# eBus_RS232_schematic.net
KiCad netlist of a schematic drawn in EAGLE
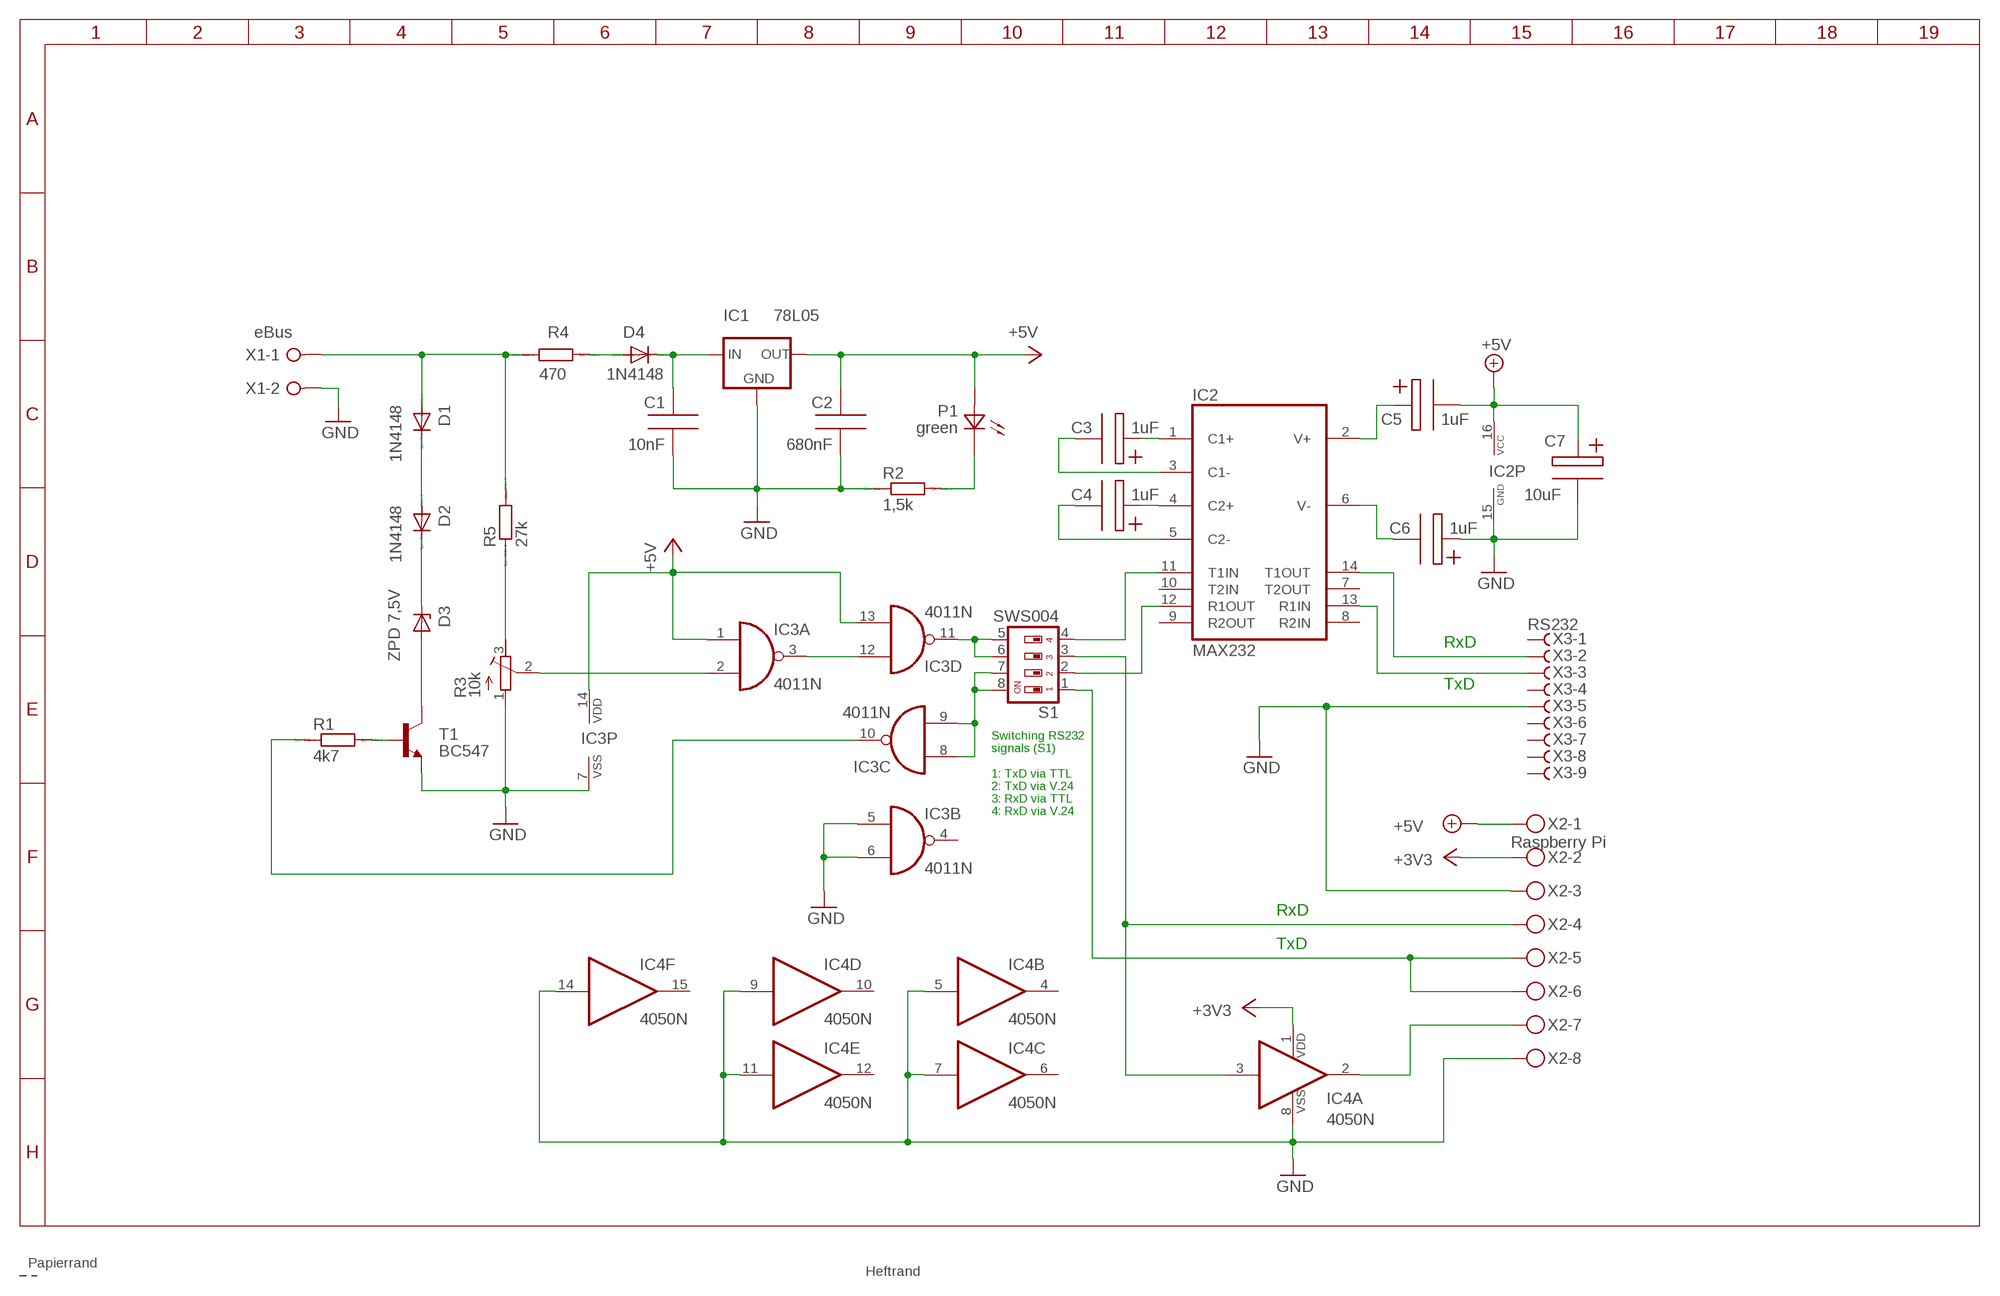
[diagram p0: schematic, sheet 1]

(export (version "E")
  (design (tool "Eeschema 10.0.6"))
  (components
    (comp (ref "C1")
      (value "10nF")
      (footprint "eagle-import:KONDENSATOR_KAPAZITAET_ALLGEMEIN")
      (libsource (lib "eagle-import") (part "KONDENSATOR_KAPAZITAET_ALLGEMEIN"))
    )
    (comp (ref "C2")
      (value "680nF")
      (footprint "eagle-import:KONDENSATOR_KAPAZITAET_ALLGEMEIN")
      (libsource (lib "eagle-import") (part "KONDENSATOR_KAPAZITAET_ALLGEMEIN"))
    )
    (comp (ref "C3")
      (value "1uF")
      (footprint "eagle-import:GEPOLTER_ELEKTROLYTKONDENSATOR")
      (libsource (lib "eagle-import") (part "GEPOLTER_ELEKTROLYTKONDENSATOR"))
    )
    (comp (ref "C4")
      (value "1uF")
      (footprint "eagle-import:GEPOLTER_ELEKTROLYTKONDENSATOR")
      (libsource (lib "eagle-import") (part "GEPOLTER_ELEKTROLYTKONDENSATOR"))
    )
    (comp (ref "C5")
      (value "1uF")
      (footprint "eagle-import:GEPOLTER_ELEKTROLYTKONDENSATOR")
      (libsource (lib "eagle-import") (part "GEPOLTER_ELEKTROLYTKONDENSATOR"))
    )
    (comp (ref "C6")
      (value "1uF")
      (footprint "eagle-import:GEPOLTER_ELEKTROLYTKONDENSATOR")
      (libsource (lib "eagle-import") (part "GEPOLTER_ELEKTROLYTKONDENSATOR"))
    )
    (comp (ref "C7")
      (value "10uF")
      (footprint "eagle-import:GEPOLTER_ELEKTROLYTKONDENSATOR")
      (libsource (lib "eagle-import") (part "GEPOLTER_ELEKTROLYTKONDENSATOR"))
    )
    (comp (ref "D1")
      (value "1N4148")
      (footprint "eagle-import:DO35-10")
      (libsource (lib "eagle-import") (part "1N4148DO35-10"))
    )
    (comp (ref "D2")
      (value "1N4148")
      (footprint "eagle-import:DO35-10")
      (libsource (lib "eagle-import") (part "1N4148DO35-10"))
    )
    (comp (ref "D3")
      (value "ZPD 7,5V")
      (footprint "eagle-import:DO35Z10")
      (libsource (lib "eagle-import") (part "ZPD"))
    )
    (comp (ref "D4")
      (value "1N4148")
      (footprint "eagle-import:DO35-10")
      (libsource (lib "eagle-import") (part "1N4148DO35-10"))
    )
    (comp (ref "IC1")
      (value "78L05")
      (footprint "eagle-import:78LXX")
      (libsource (lib "eagle-import") (part "78LXX"))
    )
    (comp (ref "IC2")
      (value "MAX232")
      (footprint "eagle-import:DIL16")
      (fields (field (name "MF") "MAXIM") (field (name "MPN") "MAX232ACPE+"))
      (libsource (lib "eagle-import") (part "MAX232"))
    )
    (comp (ref "IC3")
      (value "4011N")
      (footprint "eagle-import:DIL14")
      (libsource (lib "eagle-import") (part "4011N"))
    )
    (comp (ref "IC4")
      (value "4050N")
      (footprint "eagle-import:DIL16")
      (libsource (lib "eagle-import") (part "4050N"))
    )
    (comp (ref "P1")
      (value "green")
      (footprint "eagle-import:ANZEIGE_LEUCHTE_LED")
      (libsource (lib "eagle-import") (part "ANZEIGE_LEUCHTE_LED"))
    )
    (comp (ref "R1")
      (value "4k7")
      (footprint "eagle-import:0207_10")
      (libsource (lib "eagle-import") (part "R-EU_0207_10"))
    )
    (comp (ref "R2")
      (value "1,5k")
      (footprint "eagle-import:0207_10")
      (libsource (lib "eagle-import") (part "R-EU_0207_10"))
    )
    (comp (ref "R3")
      (value "10k")
      (footprint "eagle-import:RTRIM3339P")
      (libsource (lib "eagle-import") (part "R-TRIMM3339P"))
    )
    (comp (ref "R4")
      (value "470")
      (footprint "eagle-import:0207_10")
      (libsource (lib "eagle-import") (part "R-EU_0207_10"))
    )
    (comp (ref "R5")
      (value "27k")
      (footprint "eagle-import:0207_10")
      (libsource (lib "eagle-import") (part "R-EU_0207_10"))
    )
    (comp (ref "S1")
      (value "SWS004")
      (footprint "eagle-import:SMS-004")
      (libsource (lib "eagle-import") (part "SWS004"))
    )
    (comp (ref "T1")
      (value "BC547")
      (footprint "eagle-import:TO92")
      (libsource (lib "eagle-import") (part "BC547"))
    )
    (comp (ref "X1")
      (value "eBus")
      (footprint "eagle-import:W237-132")
      (libsource (lib "eagle-import") (part "W237-02P"))
    )
    (comp (ref "X2")
      (value "Raspberry Pi")
      (footprint "eagle-import:MKDSN1,5_8-5,08")
      (libsource (lib "eagle-import") (part "MKDSN1,5/8-5,08"))
    )
    (comp (ref "X3")
      (value "RS232")
      (footprint "eagle-import:F09V")
      (libsource (lib "eagle-import") (part "F09?SV"))
    )
  )
  (nets
    (net (code "1") (name "+3V3") (class "Default")
      (node (ref "IC4") (pin "1") (pinfunction "VDD_1") (pintype "power_in"))
      (node (ref "X2") (pin "2") (pinfunction "KL_2") (pintype "passive"))
    )
    (net (code "2") (name "+5V") (class "Default")
      (node (ref "C2") (pin "1") (pinfunction "1_1") (pintype "passive"))
      (node (ref "C5") (pin "-") (pinfunction "-_-") (pintype "passive"))
      (node (ref "C7") (pin "+") (pinfunction "+_+") (pintype "passive"))
      (node (ref "IC1") (pin "OUT") (pinfunction "OUT_OUT") (pintype "passive"))
      (node (ref "IC2") (pin "16") (pinfunction "VCC_16") (pintype "power_in"))
      (node (ref "IC3") (pin "1") (pinfunction "I0_1") (pintype "input"))
      (node (ref "IC3") (pin "13") (pinfunction "I1_13") (pintype "input"))
      (node (ref "IC3") (pin "14") (pinfunction "VDD_14") (pintype "power_in"))
      (node (ref "P1") (pin "1") (pinfunction "A_1") (pintype "input"))
      (node (ref "X2") (pin "1") (pinfunction "KL_1") (pintype "passive"))
    )
    (net (code "3") (name "GND") (class "Default")
      (node (ref "C1") (pin "2") (pinfunction "2_2") (pintype "passive"))
      (node (ref "C2") (pin "2") (pinfunction "2_2") (pintype "passive"))
      (node (ref "C6") (pin "+") (pinfunction "+_+") (pintype "passive"))
      (node (ref "C7") (pin "-") (pinfunction "-_-") (pintype "passive"))
      (node (ref "IC1") (pin "GND") (pinfunction "GND_GND") (pintype "input"))
      (node (ref "IC2") (pin "15") (pinfunction "GND_15") (pintype "power_in"))
      (node (ref "IC3") (pin "5") (pinfunction "I0_5") (pintype "input"))
      (node (ref "IC3") (pin "6") (pinfunction "I1_6") (pintype "input"))
      (node (ref "IC3") (pin "7") (pinfunction "VSS_7") (pintype "power_in"))
      (node (ref "IC4") (pin "11") (pinfunction "I_11") (pintype "input"))
      (node (ref "IC4") (pin "14") (pinfunction "I_14") (pintype "input"))
      (node (ref "IC4") (pin "5") (pinfunction "I_5") (pintype "input"))
      (node (ref "IC4") (pin "7") (pinfunction "I_7") (pintype "input"))
      (node (ref "IC4") (pin "8") (pinfunction "VSS_8") (pintype "power_in"))
      (node (ref "IC4") (pin "9") (pinfunction "I_9") (pintype "input"))
      (node (ref "R2") (pin "1") (pinfunction "1_1") (pintype "passive"))
      (node (ref "R3") (pin "1") (pinfunction "E_1") (pintype "passive"))
      (node (ref "T1") (pin "1") (pinfunction "E_1") (pintype "passive"))
      (node (ref "X1") (pin "2") (pinfunction "KL_2") (pintype "passive"))
      (node (ref "X2") (pin "3") (pinfunction "KL_3") (pintype "passive"))
      (node (ref "X2") (pin "8") (pinfunction "KL_8") (pintype "passive"))
      (node (ref "X3") (pin "5") (pinfunction "F_5") (pintype "passive"))
    )
    (net (code "4") (name "Net-(C1-Pad1)") (class "Default")
      (node (ref "C1") (pin "1") (pinfunction "1_1") (pintype "passive"))
      (node (ref "D4") (pin "C") (pinfunction "C_C") (pintype "passive"))
      (node (ref "IC1") (pin "IN") (pinfunction "IN_IN") (pintype "input"))
    )
    (net (code "5") (name "Net-(D1-PadC)") (class "Default")
      (node (ref "D1") (pin "C") (pinfunction "C_C") (pintype "passive"))
      (node (ref "D2") (pin "A") (pinfunction "A_A") (pintype "passive"))
    )
    (net (code "6") (name "Net-(D2-PadC)") (class "Default")
      (node (ref "D2") (pin "C") (pinfunction "C_C") (pintype "passive"))
      (node (ref "D3") (pin "C") (pinfunction "C_C") (pintype "passive"))
    )
    (net (code "7") (name "Net-(D4-PadA)") (class "Default")
      (node (ref "D4") (pin "A") (pinfunction "A_A") (pintype "passive"))
      (node (ref "R4") (pin "2") (pinfunction "2_2") (pintype "passive"))
    )
    (net (code "8") (name "Net-(IC2A-C1+)") (class "Default")
      (node (ref "C3") (pin "+") (pinfunction "+_+") (pintype "passive"))
      (node (ref "IC2") (pin "1") (pinfunction "C1+_1") (pintype "bidirectional"))
    )
    (net (code "9") (name "Net-(IC2A-C1-)") (class "Default")
      (node (ref "C3") (pin "-") (pinfunction "-_-") (pintype "passive"))
      (node (ref "IC2") (pin "3") (pinfunction "C1-_3") (pintype "bidirectional"))
    )
    (net (code "10") (name "Net-(IC2A-C2+)") (class "Default")
      (node (ref "C4") (pin "+") (pinfunction "+_+") (pintype "passive"))
      (node (ref "IC2") (pin "4") (pinfunction "C2+_4") (pintype "bidirectional"))
    )
    (net (code "11") (name "Net-(IC2A-C2-)") (class "Default")
      (node (ref "C4") (pin "-") (pinfunction "-_-") (pintype "passive"))
      (node (ref "IC2") (pin "5") (pinfunction "C2-_5") (pintype "bidirectional"))
    )
    (net (code "12") (name "Net-(IC2A-R1IN)") (class "Default")
      (node (ref "IC2") (pin "13") (pinfunction "R1IN_13") (pintype "input"))
      (node (ref "X3") (pin "3") (pinfunction "F_3") (pintype "passive"))
    )
    (net (code "13") (name "Net-(IC2A-R1OUT)") (class "Default")
      (node (ref "IC2") (pin "12") (pinfunction "R1OUT_12") (pintype "output"))
      (node (ref "S1") (pin "2") (pinfunction "2_2") (pintype "passive"))
    )
    (net (code "14") (name "Net-(IC2A-T1IN)") (class "Default")
      (node (ref "IC2") (pin "11") (pinfunction "T1IN_11") (pintype "input"))
      (node (ref "S1") (pin "4") (pinfunction "4_4") (pintype "passive"))
    )
    (net (code "15") (name "Net-(IC2A-T1OUT)") (class "Default")
      (node (ref "IC2") (pin "14") (pinfunction "T1OUT_14") (pintype "output"))
      (node (ref "X3") (pin "2") (pinfunction "F_2") (pintype "passive"))
    )
    (net (code "16") (name "Net-(IC2A-V+)") (class "Default")
      (node (ref "C5") (pin "+") (pinfunction "+_+") (pintype "passive"))
      (node (ref "IC2") (pin "2") (pinfunction "V+_2") (pintype "bidirectional"))
    )
    (net (code "17") (name "Net-(IC2A-V-)") (class "Default")
      (node (ref "C6") (pin "-") (pinfunction "-_-") (pintype "passive"))
      (node (ref "IC2") (pin "6") (pinfunction "V-_6") (pintype "bidirectional"))
    )
    (net (code "18") (name "Net-(IC3A-I1)") (class "Default")
      (node (ref "IC3") (pin "2") (pinfunction "I1_2") (pintype "input"))
      (node (ref "R3") (pin "2") (pinfunction "S_2") (pintype "passive"))
    )
    (net (code "19") (name "Net-(IC3A-O)") (class "Default")
      (node (ref "IC3") (pin "12") (pinfunction "I0_12") (pintype "input"))
      (node (ref "IC3") (pin "3") (pinfunction "O_3") (pintype "output"))
    )
    (net (code "20") (name "Net-(IC3C-I0)") (class "Default")
      (node (ref "IC3") (pin "8") (pinfunction "I0_8") (pintype "input"))
      (node (ref "IC3") (pin "9") (pinfunction "I1_9") (pintype "input"))
      (node (ref "S1") (pin "7") (pinfunction "7_7") (pintype "passive"))
      (node (ref "S1") (pin "8") (pinfunction "8_8") (pintype "passive"))
    )
    (net (code "21") (name "Net-(IC3C-O)") (class "Default")
      (node (ref "IC3") (pin "10") (pinfunction "O_10") (pintype "output"))
      (node (ref "R1") (pin "1") (pinfunction "1_1") (pintype "passive"))
    )
    (net (code "22") (name "Net-(IC3D-O)") (class "Default")
      (node (ref "IC3") (pin "11") (pinfunction "O_11") (pintype "output"))
      (node (ref "S1") (pin "5") (pinfunction "5_5") (pintype "passive"))
      (node (ref "S1") (pin "6") (pinfunction "6_6") (pintype "passive"))
    )
    (net (code "23") (name "Net-(IC4A-I)") (class "Default")
      (node (ref "IC4") (pin "3") (pinfunction "I_3") (pintype "input"))
      (node (ref "S1") (pin "3") (pinfunction "3_3") (pintype "passive"))
      (node (ref "X2") (pin "4") (pinfunction "KL_4") (pintype "passive"))
    )
    (net (code "24") (name "Net-(IC4A-O)") (class "Default")
      (node (ref "IC4") (pin "2") (pinfunction "O_2") (pintype "output"))
      (node (ref "X2") (pin "7") (pinfunction "KL_7") (pintype "passive"))
    )
    (net (code "25") (name "Net-(P1-C)") (class "Default")
      (node (ref "P1") (pin "2") (pinfunction "C_2") (pintype "input"))
      (node (ref "R2") (pin "2") (pinfunction "2_2") (pintype "passive"))
    )
    (net (code "26") (name "Net-(R3-A)") (class "Default")
      (node (ref "R3") (pin "3") (pinfunction "A_3") (pintype "passive"))
      (node (ref "R5") (pin "1") (pinfunction "1_1") (pintype "passive"))
    )
    (net (code "27") (name "Net-(T1-B)") (class "Default")
      (node (ref "R1") (pin "2") (pinfunction "2_2") (pintype "passive"))
      (node (ref "T1") (pin "2") (pinfunction "B_2") (pintype "passive"))
    )
    (net (code "28") (name "Net-(T1-C)") (class "Default")
      (node (ref "D3") (pin "A") (pinfunction "A_A") (pintype "passive"))
      (node (ref "T1") (pin "3") (pinfunction "C_3") (pintype "passive"))
    )
    (net (code "29") (name "Net-(X1A-KL)") (class "Default")
      (node (ref "D1") (pin "A") (pinfunction "A_A") (pintype "passive"))
      (node (ref "R4") (pin "1") (pinfunction "1_1") (pintype "passive"))
      (node (ref "R5") (pin "2") (pinfunction "2_2") (pintype "passive"))
      (node (ref "X1") (pin "1") (pinfunction "KL_1") (pintype "passive"))
    )
    (net (code "30") (name "Net-(X2E-KL)") (class "Default")
      (node (ref "S1") (pin "1") (pinfunction "1_1") (pintype "passive"))
      (node (ref "X2") (pin "5") (pinfunction "KL_5") (pintype "passive"))
      (node (ref "X2") (pin "6") (pinfunction "KL_6") (pintype "passive"))
    )
    (net (code "31") (name "unconnected-(IC2A-R2IN-Pad8)") (class "Default")
      (node (ref "IC2") (pin "8") (pinfunction "R2IN_8") (pintype "input"))
    )
    (net (code "32") (name "unconnected-(IC2A-R2OUT-Pad9)") (class "Default")
      (node (ref "IC2") (pin "9") (pinfunction "R2OUT_9") (pintype "output"))
    )
    (net (code "33") (name "unconnected-(IC2A-T2IN-Pad10)") (class "Default")
      (node (ref "IC2") (pin "10") (pinfunction "T2IN_10") (pintype "input"))
    )
    (net (code "34") (name "unconnected-(IC2A-T2OUT-Pad7)") (class "Default")
      (node (ref "IC2") (pin "7") (pinfunction "T2OUT_7") (pintype "output"))
    )
    (net (code "35") (name "unconnected-(IC3B-O-Pad4)") (class "Default")
      (node (ref "IC3") (pin "4") (pinfunction "O_4") (pintype "output"))
    )
    (net (code "36") (name "unconnected-(IC4B-O-Pad4)") (class "Default")
      (node (ref "IC4") (pin "4") (pinfunction "O_4") (pintype "output"))
    )
    (net (code "37") (name "unconnected-(IC4C-O-Pad6)") (class "Default")
      (node (ref "IC4") (pin "6") (pinfunction "O_6") (pintype "output"))
    )
    (net (code "38") (name "unconnected-(IC4D-O-Pad10)") (class "Default")
      (node (ref "IC4") (pin "10") (pinfunction "O_10") (pintype "output"))
    )
    (net (code "39") (name "unconnected-(IC4E-O-Pad12)") (class "Default")
      (node (ref "IC4") (pin "12") (pinfunction "O_12") (pintype "output"))
    )
    (net (code "40") (name "unconnected-(IC4F-O-Pad15)") (class "Default")
      (node (ref "IC4") (pin "15") (pinfunction "O_15") (pintype "output"))
    )
    (net (code "41") (name "unconnected-(X3A-F-Pad1)") (class "Default")
      (node (ref "X3") (pin "1") (pinfunction "F_1") (pintype "passive"))
    )
    (net (code "42") (name "unconnected-(X3D-F-Pad4)") (class "Default")
      (node (ref "X3") (pin "4") (pinfunction "F_4") (pintype "passive"))
    )
    (net (code "43") (name "unconnected-(X3F-F-Pad6)") (class "Default")
      (node (ref "X3") (pin "6") (pinfunction "F_6") (pintype "passive"))
    )
    (net (code "44") (name "unconnected-(X3G-F-Pad7)") (class "Default")
      (node (ref "X3") (pin "7") (pinfunction "F_7") (pintype "passive"))
    )
    (net (code "45") (name "unconnected-(X3H-F-Pad8)") (class "Default")
      (node (ref "X3") (pin "8") (pinfunction "F_8") (pintype "passive"))
    )
    (net (code "46") (name "unconnected-(X3I-F-Pad9)") (class "Default")
      (node (ref "X3") (pin "9") (pinfunction "F_9") (pintype "passive"))
    )
  )
)
